# PART3.net
KiCad netlist of a schematic drawn in Altium Designer
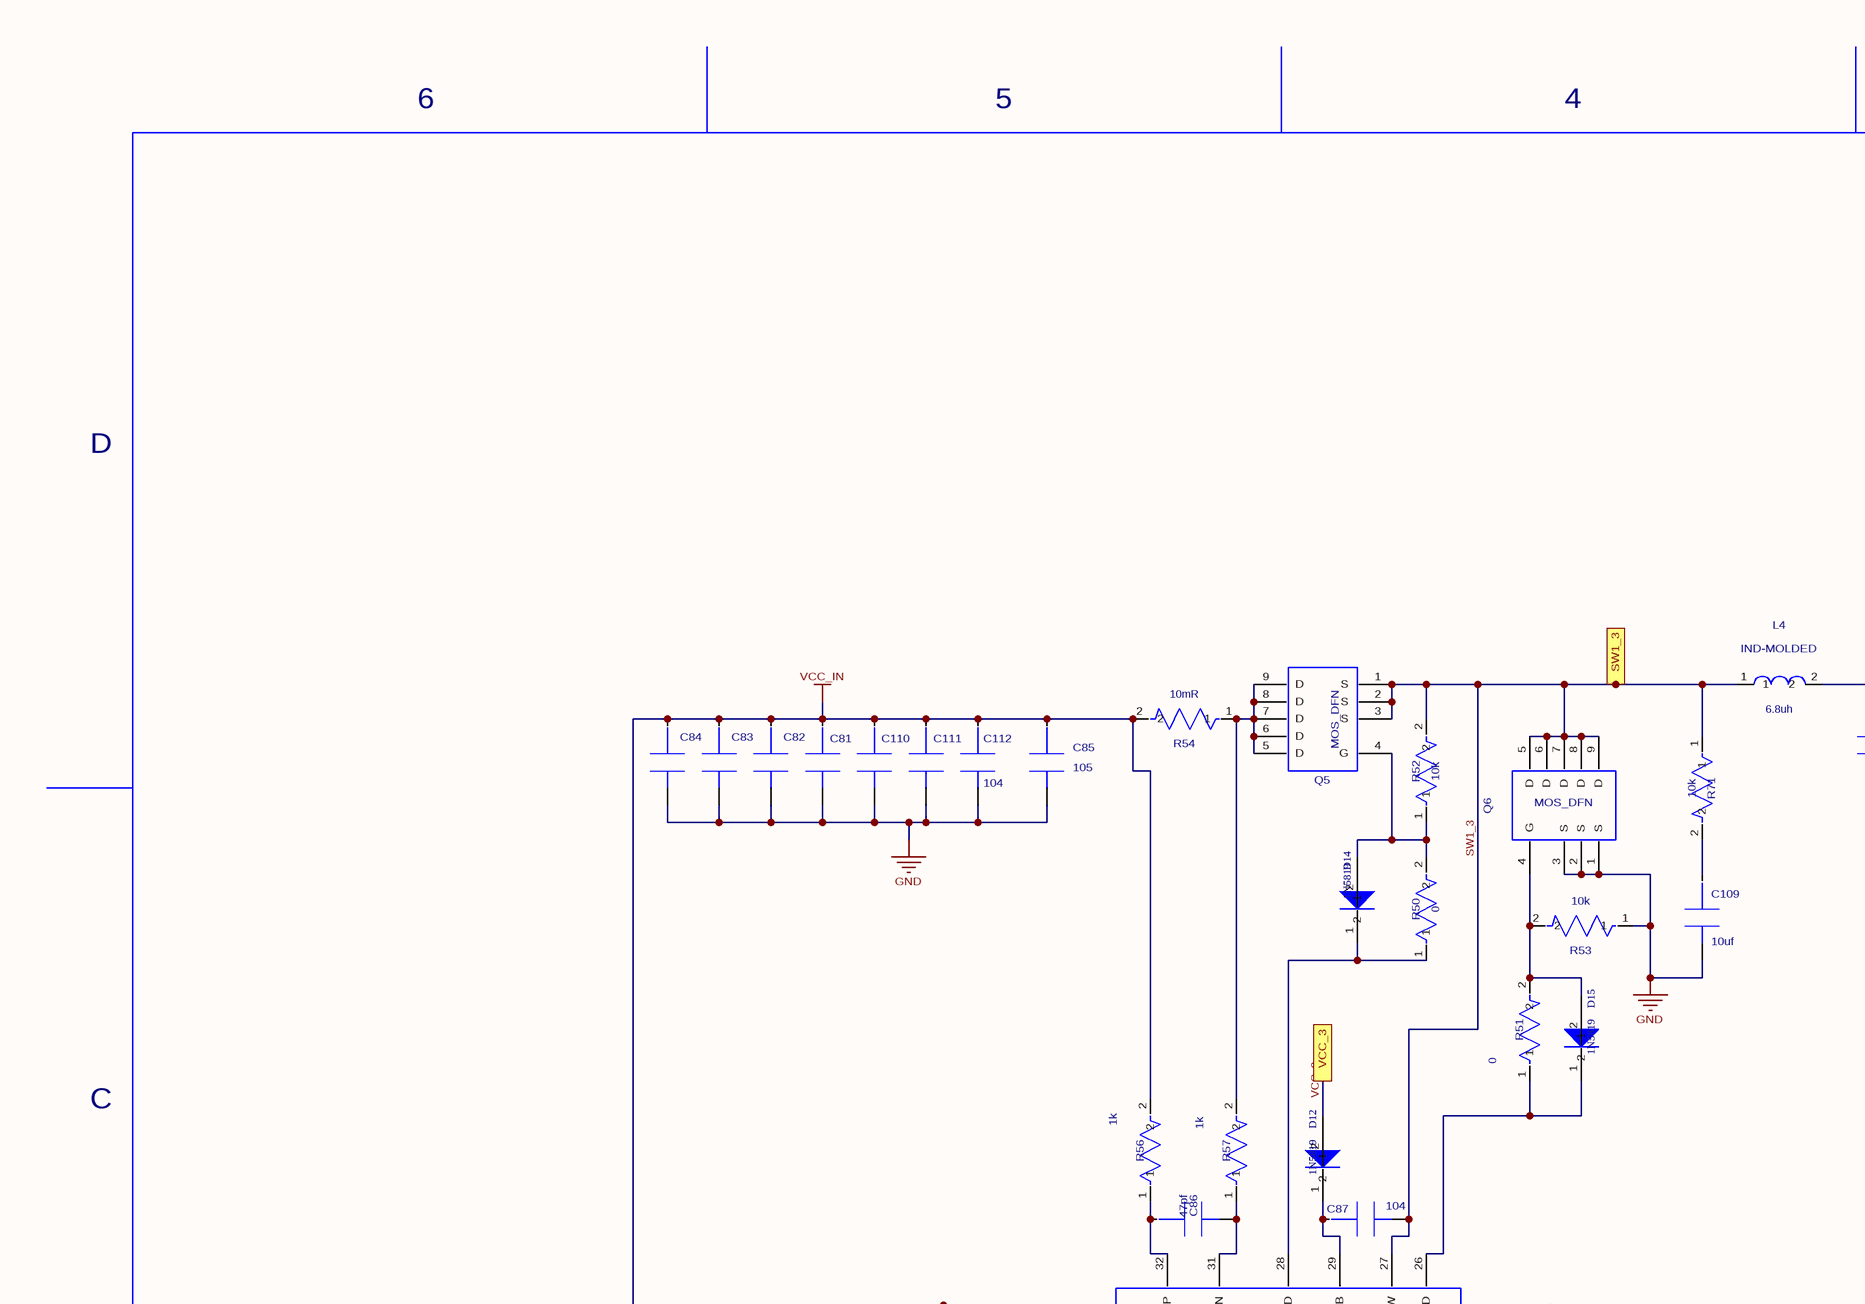
[diagram p0: PART3.SchDoc, top left]
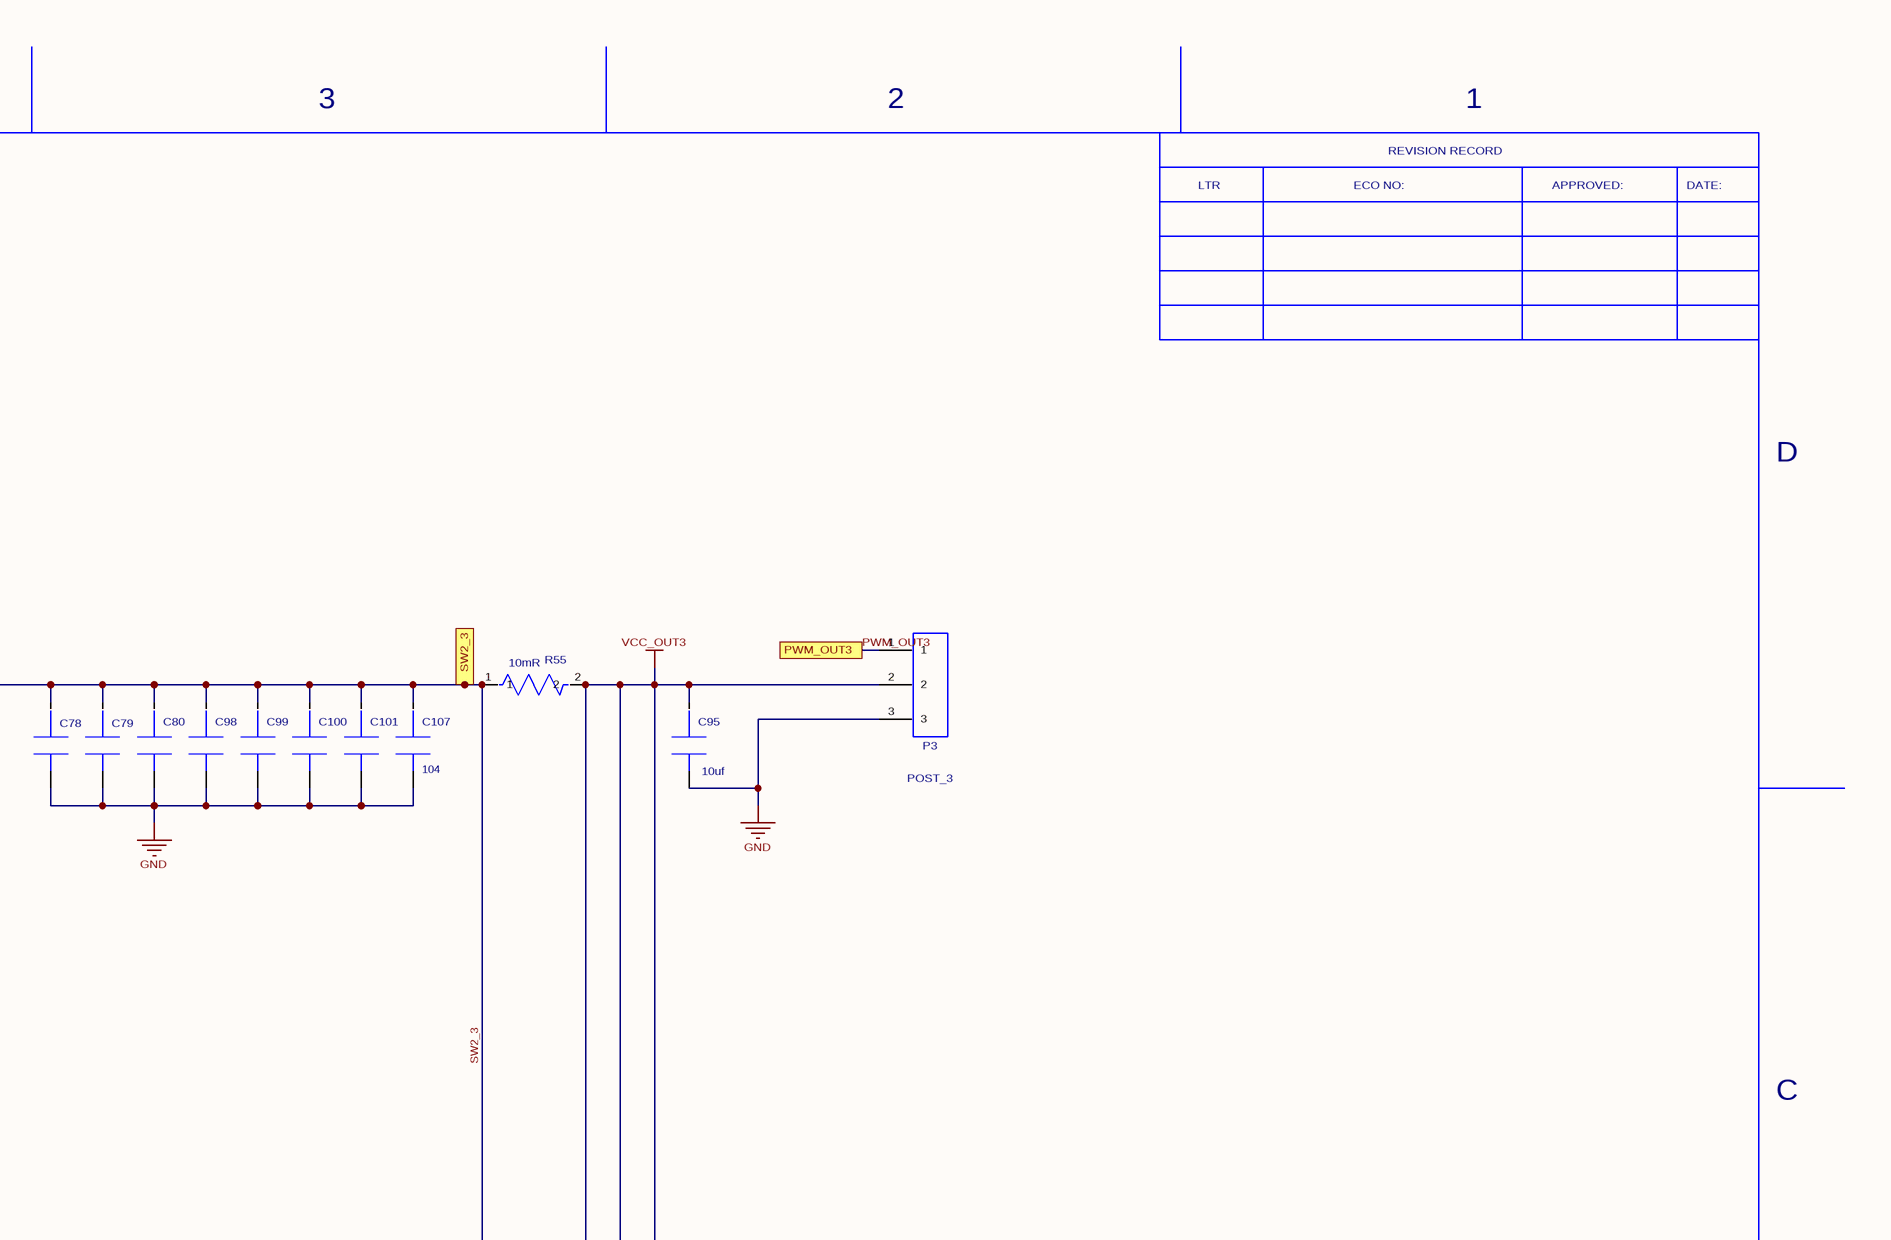
[diagram p1: PART3.SchDoc, top right]
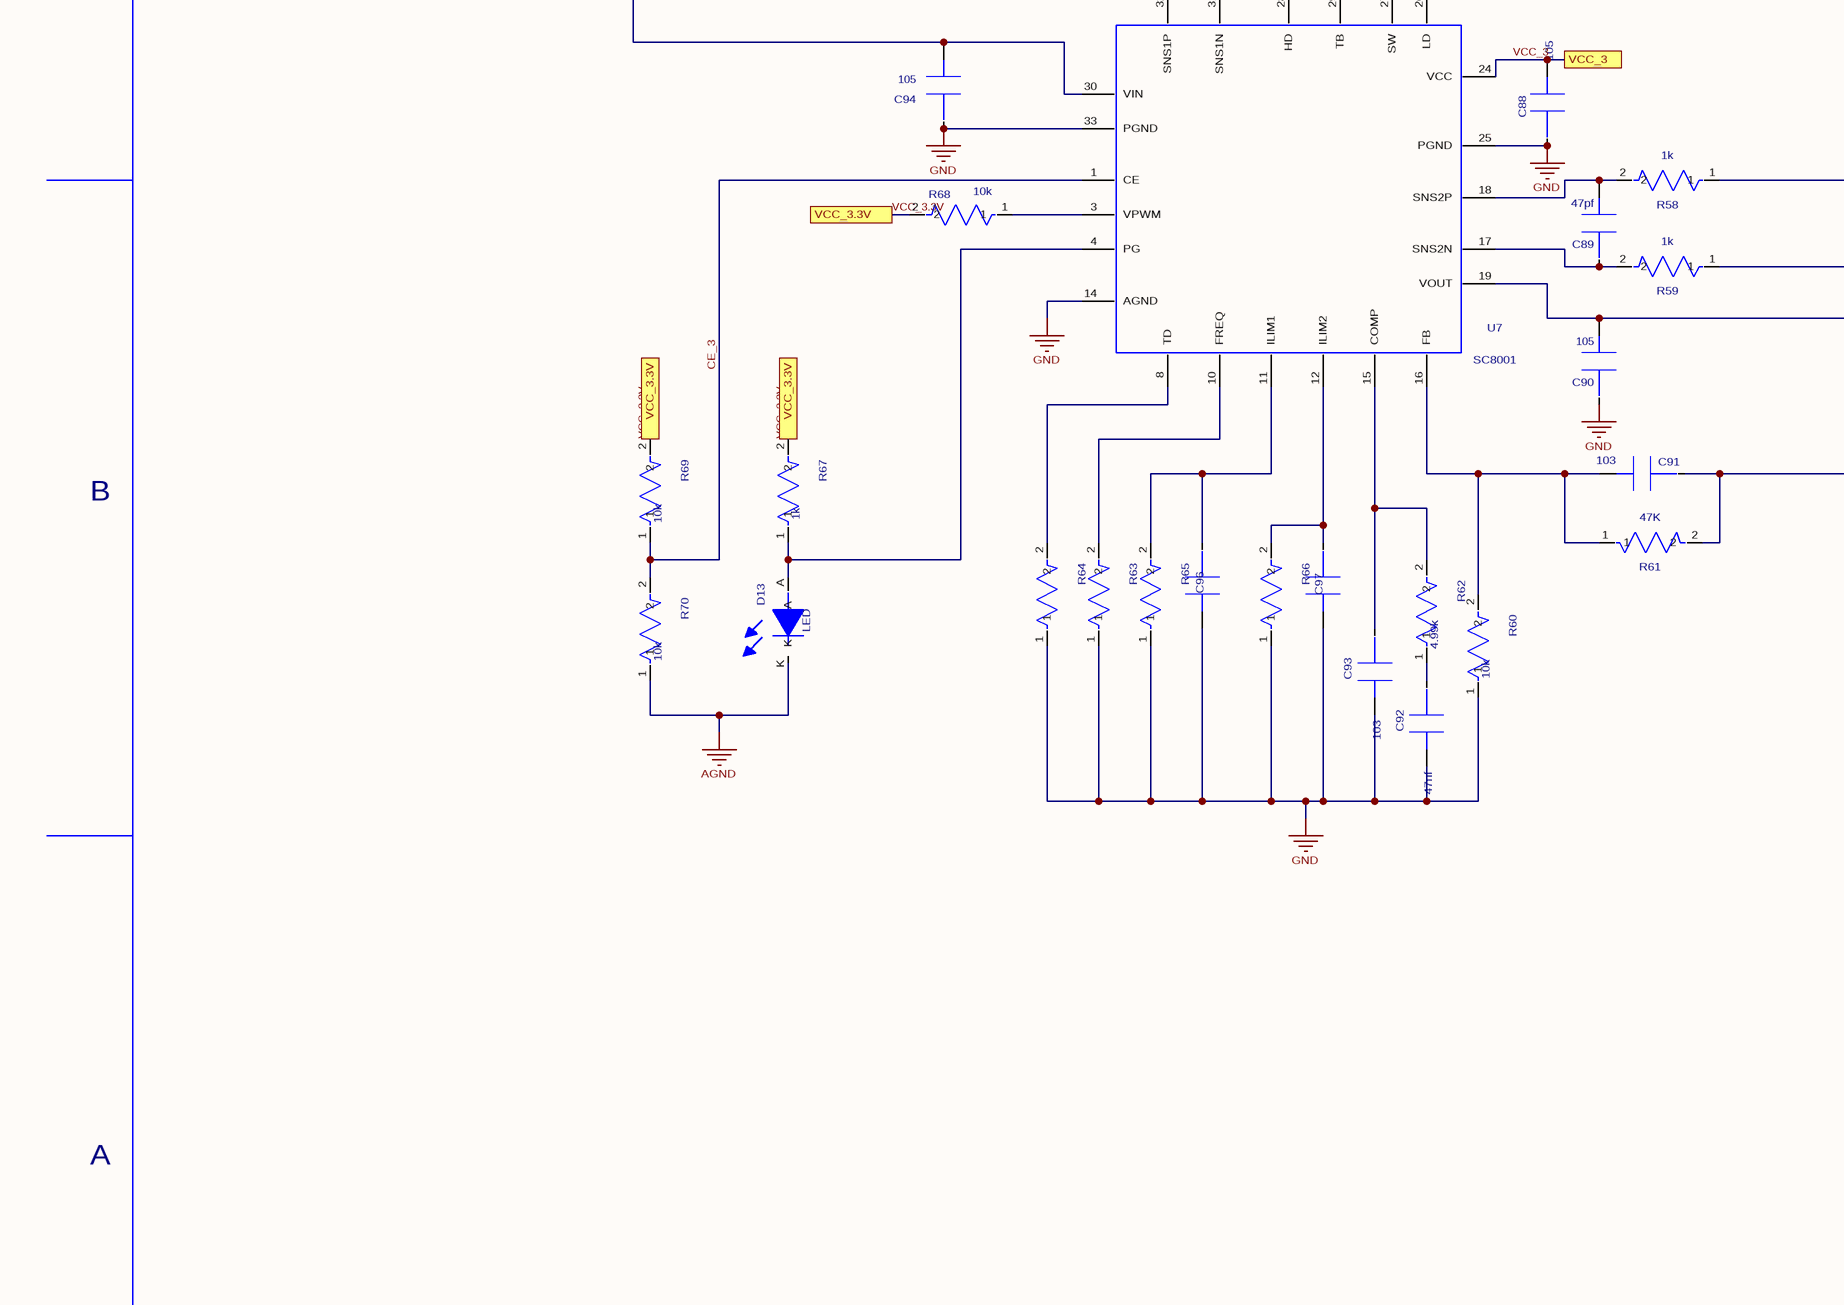
[diagram p2: PART3.SchDoc, bottom left]
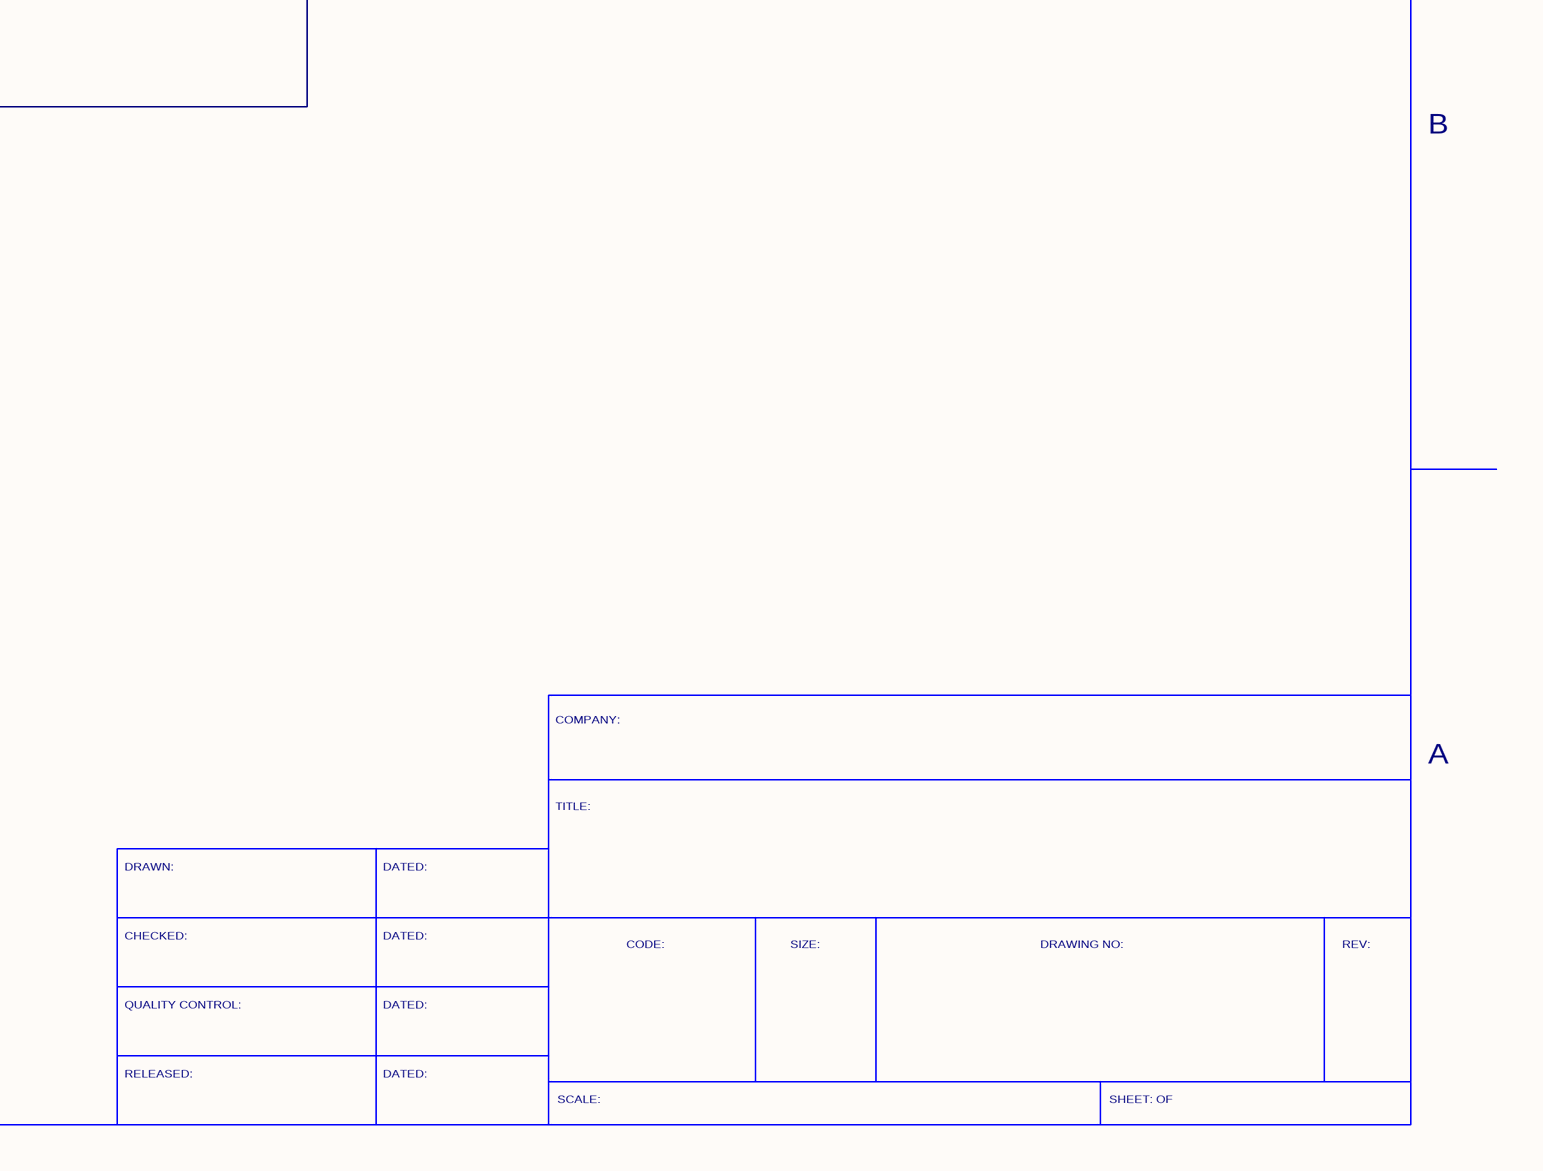
[diagram p3: PART3.SchDoc, bottom right]

(export (version "E")
  (design (tool "Eeschema 10.0.6"))
  (components
    (comp (ref "C78")
      (value "CAP-AE6.3")
      (footprint "CC6.56.5")
      (description "ALUMINUM ELECTROLYTIC CAP.")
      (libsource (lib "*") (part "CAP-AE6.3"))
    )
    (comp (ref "C79")
      (value "CAP-AE6.3")
      (footprint "CC6.56.5")
      (description "ALUMINUM ELECTROLYTIC CAP.")
      (libsource (lib "*") (part "CAP-AE6.3"))
    )
    (comp (ref "C80")
      (value "CAP-CFR04R-C")
      (footprint "1206C")
      (description "RADIAL FILM CAPACITOR, MIL-SPEC SIZE CFR04R SIZE 'C'")
      (fields (field (name "TOLERANCE") "???") (field (name "PART NUMBER") "TBD"))
      (libsource (lib "*") (part "CAP-CFR04R-C"))
    )
    (comp (ref "C81")
      (value "CAP-CFR04R-C")
      (footprint "1210C")
      (description "RADIAL FILM CAPACITOR, MIL-SPEC SIZE CFR04R SIZE 'C'")
      (fields (field (name "TOLERANCE") "???") (field (name "PART NUMBER") "TBD"))
      (libsource (lib "*") (part "CAP-CFR04R-C"))
    )
    (comp (ref "C82")
      (value "CAP-CFR04R-C")
      (footprint "1210C")
      (description "RADIAL FILM CAPACITOR, MIL-SPEC SIZE CFR04R SIZE 'C'")
      (fields (field (name "TOLERANCE") "???") (field (name "PART NUMBER") "TBD"))
      (libsource (lib "*") (part "CAP-CFR04R-C"))
    )
    (comp (ref "C83")
      (value "CAP-CFR04R-C")
      (footprint "1206C")
      (description "RADIAL FILM CAPACITOR, MIL-SPEC SIZE CFR04R SIZE 'C'")
      (fields (field (name "TOLERANCE") "???") (field (name "PART NUMBER") "TBD"))
      (libsource (lib "*") (part "CAP-CFR04R-C"))
    )
    (comp (ref "C84")
      (value "CAP-CFR04R-C")
      (footprint "1210C")
      (description "RADIAL FILM CAPACITOR, MIL-SPEC SIZE CFR04R SIZE 'C'")
      (fields (field (name "TOLERANCE") "???") (field (name "PART NUMBER") "TBD"))
      (libsource (lib "*") (part "CAP-CFR04R-C"))
    )
    (comp (ref "C85")
      (value "105")
      (footprint "0805C")
      (description "RADIAL FILM CAPACITOR, MIL-SPEC SIZE CFR04R SIZE 'C'")
      (fields (field (name "TOLERANCE") "???") (field (name "PART NUMBER") "TBD"))
      (libsource (lib "*") (part "CAP-CFR04R-C"))
    )
    (comp (ref "C86")
      (value "47pf")
      (footprint "0603C")
      (description "RADIAL FILM CAPACITOR, MIL-SPEC SIZE CFR04R SIZE 'C'")
      (fields (field (name "TOLERANCE") "???") (field (name "PART NUMBER") "TBD"))
      (libsource (lib "*") (part "CAP-CFR04R-C"))
    )
    (comp (ref "C87")
      (value "104")
      (footprint "0805C")
      (description "RADIAL FILM CAPACITOR, MIL-SPEC SIZE CFR04R SIZE 'C'")
      (fields (field (name "TOLERANCE") "???") (field (name "PART NUMBER") "TBD"))
      (libsource (lib "*") (part "CAP-CFR04R-C"))
    )
    (comp (ref "C88")
      (value "105")
      (footprint "0805C")
      (description "RADIAL FILM CAPACITOR, MIL-SPEC SIZE CFR04R SIZE 'C'")
      (fields (field (name "TOLERANCE") "???") (field (name "PART NUMBER") "TBD"))
      (libsource (lib "*") (part "CAP-CFR04R-C"))
    )
    (comp (ref "C89")
      (value "47pf")
      (footprint "0603C")
      (description "RADIAL FILM CAPACITOR, MIL-SPEC SIZE CFR04R SIZE 'C'")
      (fields (field (name "TOLERANCE") "???") (field (name "PART NUMBER") "TBD"))
      (libsource (lib "*") (part "CAP-CFR04R-C"))
    )
    (comp (ref "C90")
      (value "105")
      (footprint "0805C")
      (description "RADIAL FILM CAPACITOR, MIL-SPEC SIZE CFR04R SIZE 'C'")
      (fields (field (name "TOLERANCE") "???") (field (name "PART NUMBER") "TBD"))
      (libsource (lib "*") (part "CAP-CFR04R-C"))
    )
    (comp (ref "C91")
      (value "103")
      (footprint "0603C")
      (description "RADIAL FILM CAPACITOR, MIL-SPEC SIZE CFR04R SIZE 'C'")
      (fields (field (name "TOLERANCE") "???") (field (name "PART NUMBER") "TBD"))
      (libsource (lib "*") (part "CAP-CFR04R-C"))
    )
    (comp (ref "C92")
      (value "47nf")
      (footprint "0603C")
      (description "RADIAL FILM CAPACITOR, MIL-SPEC SIZE CFR04R SIZE 'C'")
      (fields (field (name "TOLERANCE") "???") (field (name "PART NUMBER") "TBD"))
      (libsource (lib "*") (part "CAP-CFR04R-C"))
    )
    (comp (ref "C93")
      (value "103")
      (footprint "0603C")
      (description "RADIAL FILM CAPACITOR, MIL-SPEC SIZE CFR04R SIZE 'C'")
      (fields (field (name "TOLERANCE") "???") (field (name "PART NUMBER") "TBD"))
      (libsource (lib "*") (part "CAP-CFR04R-C"))
    )
    (comp (ref "C94")
      (value "105")
      (footprint "0805C")
      (description "RADIAL FILM CAPACITOR, MIL-SPEC SIZE CFR04R SIZE 'C'")
      (fields (field (name "TOLERANCE") "???") (field (name "PART NUMBER") "TBD"))
      (libsource (lib "*") (part "CAP-CFR04R-C"))
    )
    (comp (ref "C95")
      (value "10uf")
      (footprint "1206C")
      (description "RADIAL FILM CAPACITOR, MIL-SPEC SIZE CFR04R SIZE 'C'")
      (fields (field (name "TOLERANCE") "???") (field (name "PART NUMBER") "TBD"))
      (libsource (lib "*") (part "CAP-CFR04R-C"))
    )
    (comp (ref "C96")
      (value "CAP-CFR04R-C")
      (footprint "0603C")
      (description "RADIAL FILM CAPACITOR, MIL-SPEC SIZE CFR04R SIZE 'C'")
      (fields (field (name "TOLERANCE") "???") (field (name "PART NUMBER") "TBD"))
      (libsource (lib "*") (part "CAP-CFR04R-C"))
    )
    (comp (ref "C97")
      (value "CAP-CFR04R-C")
      (footprint "0603C")
      (description "RADIAL FILM CAPACITOR, MIL-SPEC SIZE CFR04R SIZE 'C'")
      (fields (field (name "TOLERANCE") "???") (field (name "PART NUMBER") "TBD"))
      (libsource (lib "*") (part "CAP-CFR04R-C"))
    )
    (comp (ref "C98")
      (value "CAP-CFR04R-C")
      (footprint "1206C")
      (description "RADIAL FILM CAPACITOR, MIL-SPEC SIZE CFR04R SIZE 'C'")
      (fields (field (name "TOLERANCE") "???") (field (name "PART NUMBER") "TBD"))
      (libsource (lib "*") (part "CAP-CFR04R-C"))
    )
    (comp (ref "C99")
      (value "CAP-CFR04R-C")
      (footprint "1206C")
      (description "RADIAL FILM CAPACITOR, MIL-SPEC SIZE CFR04R SIZE 'C'")
      (fields (field (name "TOLERANCE") "???") (field (name "PART NUMBER") "TBD"))
      (libsource (lib "*") (part "CAP-CFR04R-C"))
    )
    (comp (ref "C100")
      (value "CAP-CFR04R-C")
      (footprint "1206C")
      (description "RADIAL FILM CAPACITOR, MIL-SPEC SIZE CFR04R SIZE 'C'")
      (fields (field (name "TOLERANCE") "???") (field (name "PART NUMBER") "TBD"))
      (libsource (lib "*") (part "CAP-CFR04R-C"))
    )
    (comp (ref "C101")
      (value "CAP-CFR04R-C")
      (footprint "1206C")
      (description "RADIAL FILM CAPACITOR, MIL-SPEC SIZE CFR04R SIZE 'C'")
      (fields (field (name "TOLERANCE") "???") (field (name "PART NUMBER") "TBD"))
      (libsource (lib "*") (part "CAP-CFR04R-C"))
    )
    (comp (ref "C107")
      (value "104")
      (footprint "1206C")
      (description "RADIAL FILM CAPACITOR, MIL-SPEC SIZE CFR04R SIZE 'C'")
      (fields (field (name "TOLERANCE") "???") (field (name "PART NUMBER") "TBD"))
      (libsource (lib "*") (part "CAP-CFR04R-C"))
    )
    (comp (ref "C109")
      (value "10uf")
      (footprint "0805C")
      (description "RADIAL FILM CAPACITOR, MIL-SPEC SIZE CFR04R SIZE 'C'")
      (fields (field (name "TOLERANCE") "???") (field (name "PART NUMBER") "TBD"))
      (libsource (lib "*") (part "CAP-CFR04R-C"))
    )
    (comp (ref "C110")
      (value "CAP-CFR04R-C")
      (footprint "1210C")
      (description "RADIAL FILM CAPACITOR, MIL-SPEC SIZE CFR04R SIZE 'C'")
      (fields (field (name "TOLERANCE") "???") (field (name "PART NUMBER") "TBD"))
      (libsource (lib "*") (part "CAP-CFR04R-C"))
    )
    (comp (ref "C111")
      (value "CAP-CFR04R-C")
      (footprint "1210C")
      (description "RADIAL FILM CAPACITOR, MIL-SPEC SIZE CFR04R SIZE 'C'")
      (fields (field (name "TOLERANCE") "???") (field (name "PART NUMBER") "TBD"))
      (libsource (lib "*") (part "CAP-CFR04R-C"))
    )
    (comp (ref "C112")
      (value "104")
      (footprint "0805C")
      (description "RADIAL FILM CAPACITOR, MIL-SPEC SIZE CFR04R SIZE 'C'")
      (fields (field (name "TOLERANCE") "???") (field (name "PART NUMBER") "TBD"))
      (libsource (lib "*") (part "CAP-CFR04R-C"))
    )
    (comp (ref "D12")
      (value "1N5819")
      (footprint "SOD-123_L2.8-W1.8-LS3.7-RD")
      (description "High Conductance Fast Diode")
      (fields (field (name "PUBLISHER") "Altium Limited"))
      (libsource (lib "*") (part "DIODE_1N4148"))
    )
    (comp (ref "D13")
      (value "LED")
      (footprint "0805D")
      (description "LIGHT EMITTING DIODE")
      (libsource (lib "*") (part "LED"))
    )
    (comp (ref "D14")
      (value "1N5819")
      (footprint "SOD-123_L2.8-W1.8-LS3.7-RD")
      (description "High Conductance Fast Diode")
      (fields (field (name "PUBLISHER") "Altium Limited"))
      (libsource (lib "*") (part "DIODE_1N4148"))
    )
    (comp (ref "D15")
      (value "1N5819")
      (footprint "SOD-123_L2.8-W1.8-LS3.7-RD")
      (description "High Conductance Fast Diode")
      (fields (field (name "PUBLISHER") "Altium Limited"))
      (libsource (lib "*") (part "DIODE_1N4148"))
    )
    (comp (ref "L4")
      (value "IND-MOLDED")
      (footprint "1040L")
      (description "MOLDED INDUCTOR, 0.5\" PIN SPACING")
      (fields (field (name "ALTIUM_VALUE") "6.8uh"))
      (libsource (lib "*") (part "IND-MOLDED"))
    )
    (comp (ref "P3") (value "POST_3") (footprint "POST_3") (libsource (lib "*") (part "POST_3")))
    (comp (ref "Q5") (value "MOS_DFN") (footprint "DFN-8_5X6") (libsource (lib "*") (part "MOS_DFN")))
    (comp (ref "Q6") (value "MOS_DFN") (footprint "DFN-8_5X6") (libsource (lib "*") (part "MOS_DFN")))
    (comp (ref "R50")
      (value "0")
      (footprint "0603R")
      (description "WIRE WOUND RESISTOR 3.4 X 7.05 MM")
      (fields (field (name "Comment") "RES-WR1"))
      (libsource (lib "*") (part "RES-WR1"))
    )
    (comp (ref "R51")
      (value "0")
      (footprint "0603R")
      (description "WIRE WOUND RESISTOR 3.4 X 7.05 MM")
      (fields (field (name "Comment") "RES-WR1"))
      (libsource (lib "*") (part "RES-WR1"))
    )
    (comp (ref "R52")
      (value "10k")
      (footprint "0603R")
      (description "WIRE WOUND RESISTOR 3.4 X 7.05 MM")
      (fields (field (name "Comment") "RES-WR1"))
      (libsource (lib "*") (part "RES-WR1"))
    )
    (comp (ref "R53")
      (value "10k")
      (footprint "0603R")
      (description "WIRE WOUND RESISTOR 3.4 X 7.05 MM")
      (fields (field (name "Comment") "RES-WR1"))
      (libsource (lib "*") (part "RES-WR1"))
    )
    (comp (ref "R54")
      (value "10mR")
      (footprint "1206C")
      (description "WIRE WOUND RESISTOR 3.4 X 7.05 MM")
      (fields (field (name "Comment") "RES-WR1"))
      (libsource (lib "*") (part "RES-WR1"))
    )
    (comp (ref "R55")
      (value "10mR")
      (footprint "1206C")
      (description "WIRE WOUND RESISTOR 3.4 X 7.05 MM")
      (fields (field (name "Comment") "RES-WR1"))
      (libsource (lib "*") (part "RES-WR1"))
    )
    (comp (ref "R56")
      (value "1k")
      (footprint "0603R")
      (description "WIRE WOUND RESISTOR 3.4 X 7.05 MM")
      (fields (field (name "Comment") "RES-WR1"))
      (libsource (lib "*") (part "RES-WR1"))
    )
    (comp (ref "R57")
      (value "1k")
      (footprint "0603R")
      (description "WIRE WOUND RESISTOR 3.4 X 7.05 MM")
      (fields (field (name "Comment") "RES-WR1"))
      (libsource (lib "*") (part "RES-WR1"))
    )
    (comp (ref "R58")
      (value "1k")
      (footprint "0603R")
      (description "WIRE WOUND RESISTOR 3.4 X 7.05 MM")
      (fields (field (name "Comment") "RES-WR1"))
      (libsource (lib "*") (part "RES-WR1"))
    )
    (comp (ref "R59")
      (value "1k")
      (footprint "0603R")
      (description "WIRE WOUND RESISTOR 3.4 X 7.05 MM")
      (fields (field (name "Comment") "RES-WR1"))
      (libsource (lib "*") (part "RES-WR1"))
    )
    (comp (ref "R60")
      (value "10k")
      (footprint "0603R")
      (description "WIRE WOUND RESISTOR 3.4 X 7.05 MM")
      (fields (field (name "Comment") "RES-WR1"))
      (libsource (lib "*") (part "RES-WR1"))
    )
    (comp (ref "R61")
      (value "47K")
      (footprint "0603R")
      (description "WIRE WOUND RESISTOR 3.4 X 7.05 MM")
      (fields (field (name "Comment") "RES-WR1"))
      (libsource (lib "*") (part "RES-WR1"))
    )
    (comp (ref "R62")
      (value "4.99k")
      (footprint "0603R")
      (description "WIRE WOUND RESISTOR 3.4 X 7.05 MM")
      (fields (field (name "Comment") "RES-WR1"))
      (libsource (lib "*") (part "RES-WR1"))
    )
    (comp (ref "R63")
      (value "RES-WR1")
      (footprint "0603R")
      (description "WIRE WOUND RESISTOR 3.4 X 7.05 MM")
      (libsource (lib "*") (part "RES-WR1"))
    )
    (comp (ref "R64")
      (value "RES-WR1")
      (footprint "0603R")
      (description "WIRE WOUND RESISTOR 3.4 X 7.05 MM")
      (libsource (lib "*") (part "RES-WR1"))
    )
    (comp (ref "R65")
      (value "RES-WR1")
      (footprint "0603R")
      (description "WIRE WOUND RESISTOR 3.4 X 7.05 MM")
      (libsource (lib "*") (part "RES-WR1"))
    )
    (comp (ref "R66")
      (value "RES-WR1")
      (footprint "0603R")
      (description "WIRE WOUND RESISTOR 3.4 X 7.05 MM")
      (libsource (lib "*") (part "RES-WR1"))
    )
    (comp (ref "R67")
      (value "1k")
      (footprint "0805R")
      (description "WIRE WOUND RESISTOR 3.4 X 7.05 MM")
      (fields (field (name "Comment") "RES-WR1"))
      (libsource (lib "*") (part "RES-WR1"))
    )
    (comp (ref "R68")
      (value "10k")
      (footprint "0805R")
      (description "WIRE WOUND RESISTOR 3.4 X 7.05 MM")
      (fields (field (name "Comment") "RES-WR1"))
      (libsource (lib "*") (part "RES-WR1"))
    )
    (comp (ref "R69")
      (value "10k")
      (footprint "0805R")
      (description "WIRE WOUND RESISTOR 3.4 X 7.05 MM")
      (fields (field (name "Comment") "RES-WR1"))
      (libsource (lib "*") (part "RES-WR1"))
    )
    (comp (ref "R70")
      (value "10k")
      (footprint "0805R")
      (description "WIRE WOUND RESISTOR 3.4 X 7.05 MM")
      (fields (field (name "Comment") "RES-WR1"))
      (libsource (lib "*") (part "RES-WR1"))
    )
    (comp (ref "R71")
      (value "10k")
      (footprint "1206C")
      (description "WIRE WOUND RESISTOR 3.4 X 7.05 MM")
      (fields (field (name "Comment") "RES-WR1"))
      (libsource (lib "*") (part "RES-WR1"))
    )
    (comp (ref "U7")
      (value "SC8001")
      (footprint "QFN-32_L4.0-W4.0-P0.40-BL-EP2.7")
      (libsource (lib "*") (part "SC8001"))
    )
  )
  (nets
    (net (code "1") (name "/CE_3") (class "Default")
      (node (ref "R69") (pin "1") (pinfunction "1_1") (pintype "passive"))
      (node (ref "R70") (pin "2") (pinfunction "2_2") (pintype "passive"))
      (node (ref "U7") (pin "1") (pinfunction "CE_1") (pintype "passive"))
    )
    (net (code "2") (name "/PWM_OUT3") (class "Default")
      (node (ref "P3") (pin "1") (pinfunction "1_1") (pintype "passive"))
    )
    (net (code "3") (name "/SW1_3") (class "Default")
      (node (ref "C87") (pin "2") (pinfunction "2_2") (pintype "passive"))
      (node (ref "L4") (pin "1") (pinfunction "1_1") (pintype "passive"))
      (node (ref "Q5") (pin "1") (pinfunction "S_1") (pintype "passive"))
      (node (ref "Q5") (pin "2") (pinfunction "S_2") (pintype "passive"))
      (node (ref "Q5") (pin "3") (pinfunction "S_3") (pintype "passive"))
      (node (ref "Q6") (pin "5") (pinfunction "D_5") (pintype "passive"))
      (node (ref "Q6") (pin "6") (pinfunction "D_6") (pintype "passive"))
      (node (ref "Q6") (pin "7") (pinfunction "D_7") (pintype "passive"))
      (node (ref "Q6") (pin "8") (pinfunction "D_8") (pintype "passive"))
      (node (ref "Q6") (pin "9") (pinfunction "D_9") (pintype "passive"))
      (node (ref "R52") (pin "2") (pinfunction "2_2") (pintype "passive"))
      (node (ref "R71") (pin "1") (pinfunction "1_1") (pintype "passive"))
      (node (ref "U7") (pin "27") (pinfunction "SW_27") (pintype "passive"))
    )
    (net (code "4") (name "/SW2_3") (class "Default")
      (node (ref "C100") (pin "1") (pinfunction "1_1") (pintype "passive"))
      (node (ref "C101") (pin "1") (pinfunction "1_1") (pintype "passive"))
      (node (ref "C107") (pin "1") (pinfunction "1_1") (pintype "passive"))
      (node (ref "C78") (pin "1") (pinfunction "1_1") (pintype "passive"))
      (node (ref "C79") (pin "1") (pinfunction "1_1") (pintype "passive"))
      (node (ref "C80") (pin "1") (pinfunction "1_1") (pintype "passive"))
      (node (ref "C98") (pin "1") (pinfunction "1_1") (pintype "passive"))
      (node (ref "C99") (pin "1") (pinfunction "1_1") (pintype "passive"))
      (node (ref "L4") (pin "2") (pinfunction "2_2") (pintype "passive"))
      (node (ref "R55") (pin "1") (pinfunction "1_1") (pintype "passive"))
      (node (ref "R58") (pin "1") (pinfunction "1_1") (pintype "passive"))
    )
    (net (code "5") (name "/VCC_3") (class "Default")
      (node (ref "C88") (pin "2") (pinfunction "2_2") (pintype "passive"))
      (node (ref "D12") (pin "2") (pinfunction "2_2") (pintype "passive"))
      (node (ref "U7") (pin "24") (pinfunction "VCC_24") (pintype "passive"))
    )
    (net (code "6") (name "/VCC_3.3V") (class "Default")
      (node (ref "R67") (pin "2") (pinfunction "2_2") (pintype "passive"))
      (node (ref "R68") (pin "2") (pinfunction "2_2") (pintype "passive"))
      (node (ref "R69") (pin "2") (pinfunction "2_2") (pintype "passive"))
    )
    (net (code "7") (name "AGND") (class "Default")
      (node (ref "D13") (pin "K") (pinfunction "K_K") (pintype "passive"))
      (node (ref "R70") (pin "1") (pinfunction "1_1") (pintype "passive"))
    )
    (net (code "8") (name "GND") (class "Default")
      (node (ref "C100") (pin "2") (pinfunction "2_2") (pintype "passive"))
      (node (ref "C101") (pin "2") (pinfunction "2_2") (pintype "passive"))
      (node (ref "C107") (pin "2") (pinfunction "2_2") (pintype "passive"))
      (node (ref "C109") (pin "2") (pinfunction "2_2") (pintype "passive"))
      (node (ref "C110") (pin "2") (pinfunction "2_2") (pintype "passive"))
      (node (ref "C111") (pin "2") (pinfunction "2_2") (pintype "passive"))
      (node (ref "C112") (pin "2") (pinfunction "2_2") (pintype "passive"))
      (node (ref "C78") (pin "2") (pinfunction "2_2") (pintype "passive"))
      (node (ref "C79") (pin "2") (pinfunction "2_2") (pintype "passive"))
      (node (ref "C80") (pin "2") (pinfunction "2_2") (pintype "passive"))
      (node (ref "C81") (pin "2") (pinfunction "2_2") (pintype "passive"))
      (node (ref "C82") (pin "2") (pinfunction "2_2") (pintype "passive"))
      (node (ref "C83") (pin "2") (pinfunction "2_2") (pintype "passive"))
      (node (ref "C84") (pin "2") (pinfunction "2_2") (pintype "passive"))
      (node (ref "C85") (pin "2") (pinfunction "2_2") (pintype "passive"))
      (node (ref "C88") (pin "1") (pinfunction "1_1") (pintype "passive"))
      (node (ref "C90") (pin "1") (pinfunction "1_1") (pintype "passive"))
      (node (ref "C92") (pin "2") (pinfunction "2_2") (pintype "passive"))
      (node (ref "C93") (pin "2") (pinfunction "2_2") (pintype "passive"))
      (node (ref "C94") (pin "1") (pinfunction "1_1") (pintype "passive"))
      (node (ref "C95") (pin "2") (pinfunction "2_2") (pintype "passive"))
      (node (ref "C96") (pin "2") (pinfunction "2_2") (pintype "passive"))
      (node (ref "C97") (pin "2") (pinfunction "2_2") (pintype "passive"))
      (node (ref "C98") (pin "2") (pinfunction "2_2") (pintype "passive"))
      (node (ref "C99") (pin "2") (pinfunction "2_2") (pintype "passive"))
      (node (ref "P3") (pin "3") (pinfunction "3_3") (pintype "passive"))
      (node (ref "Q6") (pin "1") (pinfunction "S_1") (pintype "passive"))
      (node (ref "Q6") (pin "2") (pinfunction "S_2") (pintype "passive"))
      (node (ref "Q6") (pin "3") (pinfunction "S_3") (pintype "passive"))
      (node (ref "R53") (pin "1") (pinfunction "1_1") (pintype "passive"))
      (node (ref "R60") (pin "1") (pinfunction "1_1") (pintype "passive"))
      (node (ref "R63") (pin "1") (pinfunction "1_1") (pintype "passive"))
      (node (ref "R64") (pin "1") (pinfunction "1_1") (pintype "passive"))
      (node (ref "R65") (pin "1") (pinfunction "1_1") (pintype "passive"))
      (node (ref "R66") (pin "1") (pinfunction "1_1") (pintype "passive"))
      (node (ref "U7") (pin "14") (pinfunction "AGND_14") (pintype "passive"))
      (node (ref "U7") (pin "25") (pinfunction "PGND_25") (pintype "passive"))
      (node (ref "U7") (pin "33") (pinfunction "PGND_33") (pintype "passive"))
    )
    (net (code "9") (name "Net-(C92-Pad1)") (class "Default")
      (node (ref "C92") (pin "1") (pinfunction "1_1") (pintype "passive"))
      (node (ref "R62") (pin "1") (pinfunction "1_1") (pintype "passive"))
    )
    (net (code "10") (name "Net-(C109-Pad1)") (class "Default")
      (node (ref "C109") (pin "1") (pinfunction "1_1") (pintype "passive"))
      (node (ref "R71") (pin "2") (pinfunction "2_2") (pintype "passive"))
    )
    (net (code "11") (name "Net-(Q5-D-Pad5)") (class "Default")
      (node (ref "Q5") (pin "5") (pinfunction "D_5") (pintype "passive"))
      (node (ref "Q5") (pin "6") (pinfunction "D_6") (pintype "passive"))
      (node (ref "Q5") (pin "7") (pinfunction "D_7") (pintype "passive"))
      (node (ref "Q5") (pin "8") (pinfunction "D_8") (pintype "passive"))
      (node (ref "Q5") (pin "9") (pinfunction "D_9") (pintype "passive"))
      (node (ref "R54") (pin "1") (pinfunction "1_1") (pintype "passive"))
      (node (ref "R57") (pin "2") (pinfunction "2_2") (pintype "passive"))
    )
    (net (code "12") (name "Net-(Q5-G)") (class "Default")
      (node (ref "D14") (pin "2") (pinfunction "2_2") (pintype "passive"))
      (node (ref "Q5") (pin "4") (pinfunction "G_4") (pintype "passive"))
      (node (ref "R50") (pin "2") (pinfunction "2_2") (pintype "passive"))
      (node (ref "R52") (pin "1") (pinfunction "1_1") (pintype "passive"))
    )
    (net (code "13") (name "Net-(Q6-G)") (class "Default")
      (node (ref "D15") (pin "2") (pinfunction "2_2") (pintype "passive"))
      (node (ref "Q6") (pin "4") (pinfunction "G_4") (pintype "passive"))
      (node (ref "R51") (pin "2") (pinfunction "2_2") (pintype "passive"))
      (node (ref "R53") (pin "2") (pinfunction "2_2") (pintype "passive"))
    )
    (net (code "14") (name "Net-(U7-COMP)") (class "Default")
      (node (ref "C93") (pin "1") (pinfunction "1_1") (pintype "passive"))
      (node (ref "R62") (pin "2") (pinfunction "2_2") (pintype "passive"))
      (node (ref "U7") (pin "15") (pinfunction "COMP_15") (pintype "passive"))
    )
    (net (code "15") (name "Net-(U7-FB)") (class "Default")
      (node (ref "C91") (pin "2") (pinfunction "2_2") (pintype "passive"))
      (node (ref "R60") (pin "2") (pinfunction "2_2") (pintype "passive"))
      (node (ref "R61") (pin "1") (pinfunction "1_1") (pintype "passive"))
      (node (ref "U7") (pin "16") (pinfunction "FB_16") (pintype "passive"))
    )
    (net (code "16") (name "Net-(U7-FREQ)") (class "Default")
      (node (ref "R63") (pin "2") (pinfunction "2_2") (pintype "passive"))
      (node (ref "U7") (pin "10") (pinfunction "FREQ_10") (pintype "passive"))
    )
    (net (code "17") (name "Net-(U7-HD)") (class "Default")
      (node (ref "D14") (pin "1") (pinfunction "1_1") (pintype "passive"))
      (node (ref "R50") (pin "1") (pinfunction "1_1") (pintype "passive"))
      (node (ref "U7") (pin "28") (pinfunction "HD_28") (pintype "passive"))
    )
    (net (code "18") (name "Net-(U7-ILIM1)") (class "Default")
      (node (ref "C96") (pin "1") (pinfunction "1_1") (pintype "passive"))
      (node (ref "R65") (pin "2") (pinfunction "2_2") (pintype "passive"))
      (node (ref "U7") (pin "11") (pinfunction "ILIM1_11") (pintype "passive"))
    )
    (net (code "19") (name "Net-(U7-ILIM2)") (class "Default")
      (node (ref "C97") (pin "1") (pinfunction "1_1") (pintype "passive"))
      (node (ref "R66") (pin "2") (pinfunction "2_2") (pintype "passive"))
      (node (ref "U7") (pin "12") (pinfunction "ILIM2_12") (pintype "passive"))
    )
    (net (code "20") (name "Net-(U7-LD)") (class "Default")
      (node (ref "D15") (pin "1") (pinfunction "1_1") (pintype "passive"))
      (node (ref "R51") (pin "1") (pinfunction "1_1") (pintype "passive"))
      (node (ref "U7") (pin "26") (pinfunction "LD_26") (pintype "passive"))
    )
    (net (code "21") (name "Net-(U7-PG)") (class "Default")
      (node (ref "D13") (pin "A") (pinfunction "A_A") (pintype "passive"))
      (node (ref "R67") (pin "1") (pinfunction "1_1") (pintype "passive"))
      (node (ref "U7") (pin "4") (pinfunction "PG_4") (pintype "passive"))
    )
    (net (code "22") (name "Net-(U7-SNS1N)") (class "Default")
      (node (ref "C86") (pin "2") (pinfunction "2_2") (pintype "passive"))
      (node (ref "R57") (pin "1") (pinfunction "1_1") (pintype "passive"))
      (node (ref "U7") (pin "31") (pinfunction "SNS1N_31") (pintype "passive"))
    )
    (net (code "23") (name "Net-(U7-SNS1P)") (class "Default")
      (node (ref "C86") (pin "1") (pinfunction "1_1") (pintype "passive"))
      (node (ref "R56") (pin "1") (pinfunction "1_1") (pintype "passive"))
      (node (ref "U7") (pin "32") (pinfunction "SNS1P_32") (pintype "passive"))
    )
    (net (code "24") (name "Net-(U7-SNS2N)") (class "Default")
      (node (ref "C89") (pin "1") (pinfunction "1_1") (pintype "passive"))
      (node (ref "R59") (pin "2") (pinfunction "2_2") (pintype "passive"))
      (node (ref "U7") (pin "17") (pinfunction "SNS2N_17") (pintype "passive"))
    )
    (net (code "25") (name "Net-(U7-SNS2P)") (class "Default")
      (node (ref "C89") (pin "2") (pinfunction "2_2") (pintype "passive"))
      (node (ref "R58") (pin "2") (pinfunction "2_2") (pintype "passive"))
      (node (ref "U7") (pin "18") (pinfunction "SNS2P_18") (pintype "passive"))
    )
    (net (code "26") (name "Net-(U7-TB)") (class "Default")
      (node (ref "C87") (pin "1") (pinfunction "1_1") (pintype "passive"))
      (node (ref "D12") (pin "1") (pinfunction "1_1") (pintype "passive"))
      (node (ref "U7") (pin "29") (pinfunction "TB_29") (pintype "passive"))
    )
    (net (code "27") (name "Net-(U7-TD)") (class "Default")
      (node (ref "R64") (pin "2") (pinfunction "2_2") (pintype "passive"))
      (node (ref "U7") (pin "8") (pinfunction "TD_8") (pintype "passive"))
    )
    (net (code "28") (name "Net-(U7-VPWM)") (class "Default")
      (node (ref "R68") (pin "1") (pinfunction "1_1") (pintype "passive"))
      (node (ref "U7") (pin "3") (pinfunction "VPWM_3") (pintype "passive"))
    )
    (net (code "29") (name "VCC_IN") (class "Default")
      (node (ref "C110") (pin "1") (pinfunction "1_1") (pintype "passive"))
      (node (ref "C111") (pin "1") (pinfunction "1_1") (pintype "passive"))
      (node (ref "C112") (pin "1") (pinfunction "1_1") (pintype "passive"))
      (node (ref "C81") (pin "1") (pinfunction "1_1") (pintype "passive"))
      (node (ref "C82") (pin "1") (pinfunction "1_1") (pintype "passive"))
      (node (ref "C83") (pin "1") (pinfunction "1_1") (pintype "passive"))
      (node (ref "C84") (pin "1") (pinfunction "1_1") (pintype "passive"))
      (node (ref "C85") (pin "1") (pinfunction "1_1") (pintype "passive"))
      (node (ref "C94") (pin "2") (pinfunction "2_2") (pintype "passive"))
      (node (ref "R54") (pin "2") (pinfunction "2_2") (pintype "passive"))
      (node (ref "R56") (pin "2") (pinfunction "2_2") (pintype "passive"))
      (node (ref "U7") (pin "30") (pinfunction "VIN_30") (pintype "passive"))
    )
    (net (code "30") (name "VCC_OUT3") (class "Default")
      (node (ref "C90") (pin "2") (pinfunction "2_2") (pintype "passive"))
      (node (ref "C91") (pin "1") (pinfunction "1_1") (pintype "passive"))
      (node (ref "C95") (pin "1") (pinfunction "1_1") (pintype "passive"))
      (node (ref "P3") (pin "2") (pinfunction "2_2") (pintype "passive"))
      (node (ref "R55") (pin "2") (pinfunction "2_2") (pintype "passive"))
      (node (ref "R59") (pin "1") (pinfunction "1_1") (pintype "passive"))
      (node (ref "R61") (pin "2") (pinfunction "2_2") (pintype "passive"))
      (node (ref "U7") (pin "19") (pinfunction "VOUT_19") (pintype "passive"))
    )
  )
)
